# Sheet2.net
KiCad netlist of a schematic drawn in Altium Designer
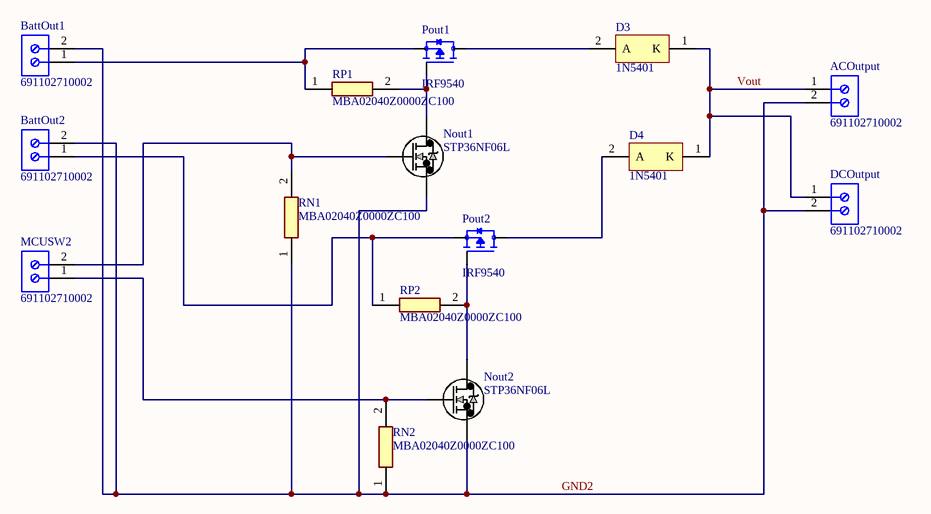
[diagram p0: Sheet2.SchDoc]

(export (version "E")
  (design (tool "Eeschema 10.0.6"))
  (components
    (comp (ref "ACOutput")
      (value "691102710002")
      (footprint "691102710002")
      (description "Series 102 - 5.00 mm Horizontal Entry Modular with Pressure Clamp WR-TBL, 2 pin")
      (fields (field (name "MANUFACTURER") "Wurth Elektronik") (field (name "PUBLISHER") "WurthElektronik"))
      (libsource (lib "Altium Content Vault") (part "WE-CN-1P-F-TB2"))
    )
    (comp (ref "BattOut1")
      (value "691102710002")
      (footprint "691102710002")
      (description "Series 102 - 5.00 mm Horizontal Entry Modular with Pressure Clamp WR-TBL, 2 pin")
      (fields (field (name "MANUFACTURER") "Wurth Elektronik") (field (name "PUBLISHER") "WurthElektronik"))
      (libsource (lib "Altium Content Vault") (part "WE-CN-1P-F-TB2"))
    )
    (comp (ref "BattOut2")
      (value "691102710002")
      (footprint "691102710002")
      (description "Series 102 - 5.00 mm Horizontal Entry Modular with Pressure Clamp WR-TBL, 2 pin")
      (fields (field (name "MANUFACTURER") "Wurth Elektronik") (field (name "PUBLISHER") "WurthElektronik"))
      (libsource (lib "Altium Content Vault") (part "WE-CN-1P-F-TB2"))
    )
    (comp (ref "D3")
      (value "1N5401")
      (footprint "ONSC-AXIAL_LEAD-2-267-05_V")
      (description "Standard Recovery Rectifier, 2-Pin Axial_Lead, Pb-Free, Bulk Box")
      (fields (field (name "MANUFACTURER") "On Semiconductor"))
      (libsource (lib "Altium Content Vault") (part "ONSC-D-K1A2-2_A"))
    )
    (comp (ref "D4")
      (value "1N5401")
      (footprint "ONSC-AXIAL_LEAD-2-267-05_V")
      (description "Standard Recovery Rectifier, 2-Pin Axial_Lead, Pb-Free, Bulk Box")
      (fields (field (name "MANUFACTURER") "On Semiconductor"))
      (libsource (lib "Altium Content Vault") (part "ONSC-D-K1A2-2_A"))
    )
    (comp (ref "DCOutput")
      (value "691102710002")
      (footprint "691102710002")
      (description "Series 102 - 5.00 mm Horizontal Entry Modular with Pressure Clamp WR-TBL, 2 pin")
      (fields (field (name "MANUFACTURER") "Wurth Elektronik") (field (name "PUBLISHER") "WurthElektronik"))
      (libsource (lib "Altium Content Vault") (part "WE-CN-1P-F-TB2"))
    )
    (comp (ref "MCUSW2")
      (value "691102710002")
      (footprint "691102710002")
      (description "Series 102 - 5.00 mm Horizontal Entry Modular with Pressure Clamp WR-TBL, 2 pin")
      (fields (field (name "MANUFACTURER") "Wurth Elektronik") (field (name "PUBLISHER") "WurthElektronik"))
      (libsource (lib "Altium Content Vault") (part "WE-CN-1P-F-TB2"))
    )
    (comp (ref "Nout1")
      (value "STP36NF06L")
      (footprint "TO-220_STM")
      (description "No Description Available")
      (fields (field (name "COPYRIGHT") "Copyright (C) 2022 Ultra Librarian. All rights reserved."))
      (libsource (lib "Schlib1") (part "STP36NF06L"))
    )
    (comp (ref "Nout2")
      (value "STP36NF06L")
      (footprint "TO-220_STM")
      (description "No Description Available")
      (fields (field (name "COPYRIGHT") "Copyright (C) 2022 Ultra Librarian. All rights reserved."))
      (libsource (lib "Schlib1") (part "STP36NF06L"))
    )
    (comp (ref "Pout1")
      (value "IRF9540")
      (footprint "TO254P1052X465X1989-3")
      (description "P-Channel 100V 19A (Tc) 150W (Tc) Through Hole TO-220AB")
      (fields (field (name "MF") "Vishay Siliconix") (field (name "DIGI-KEY_PART_NUMBER") "IRF9540PBF-ND"))
      (libsource (lib "IRF9540") (part "IRF9540"))
    )
    (comp (ref "Pout2")
      (value "IRF9540")
      (footprint "TO254P1052X465X1989-3")
      (description "P-Channel 100V 19A (Tc) 150W (Tc) Through Hole TO-220AB")
      (fields (field (name "MF") "Vishay Siliconix") (field (name "DIGI-KEY_PART_NUMBER") "IRF9540PBF-ND"))
      (libsource (lib "IRF9540") (part "IRF9540"))
    )
    (comp (ref "RN1")
      (value "MBA02040Z0000ZC100")
      (footprint "SamacSys:RESAD1000W50L360D160")
      (description "Resistor")
      (libsource (lib "") (part "MBA02040Z0000ZC100_1"))
    )
    (comp (ref "RN2")
      (value "MBA02040Z0000ZC100")
      (footprint "SamacSys:RESAD1000W50L360D160")
      (description "Resistor")
      (libsource (lib "") (part "MBA02040Z0000ZC100_1"))
    )
    (comp (ref "RP1")
      (value "MBA02040Z0000ZC100")
      (footprint "SamacSys:RESAD1000W50L360D160")
      (description "Resistor")
      (libsource (lib "*") (part "MBA02040Z0000ZC100"))
    )
    (comp (ref "RP2")
      (value "MBA02040Z0000ZC100")
      (footprint "SamacSys:RESAD1000W50L360D160")
      (description "Resistor")
      (libsource (lib "*") (part "MBA02040Z0000ZC100"))
    )
  )
  (nets
    (net (code "1") (name "/GND2") (class "Default")
      (node (ref "ACOutput") (pin "2") (pinfunction "2_2") (pintype "passive"))
      (node (ref "BattOut1") (pin "2") (pinfunction "2_2") (pintype "passive"))
      (node (ref "BattOut2") (pin "2") (pinfunction "2_2") (pintype "passive"))
      (node (ref "DCOutput") (pin "2") (pinfunction "2_2") (pintype "passive"))
      (node (ref "Nout1") (pin "3") (pinfunction "3_3") (pintype "passive"))
      (node (ref "Nout2") (pin "3") (pinfunction "3_3") (pintype "passive"))
      (node (ref "RN1") (pin "1") (pinfunction "1_1") (pintype "passive"))
      (node (ref "RN2") (pin "1") (pinfunction "1_1") (pintype "passive"))
    )
    (net (code "2") (name "/Vout") (class "Default")
      (node (ref "ACOutput") (pin "1") (pinfunction "1_1") (pintype "passive"))
      (node (ref "D3") (pin "1") (pinfunction "K_1") (pintype "passive"))
      (node (ref "D4") (pin "1") (pinfunction "K_1") (pintype "passive"))
      (node (ref "DCOutput") (pin "1") (pinfunction "1_1") (pintype "passive"))
    )
    (net (code "3") (name "Net-(D3-A)") (class "Default")
      (node (ref "D3") (pin "2") (pinfunction "A_2") (pintype "passive"))
      (node (ref "Pout1") (pin "2") (pinfunction "D_2") (pintype "passive"))
    )
    (net (code "4") (name "Net-(D4-A)") (class "Default")
      (node (ref "D4") (pin "2") (pinfunction "A_2") (pintype "passive"))
      (node (ref "Pout2") (pin "2") (pinfunction "D_2") (pintype "passive"))
    )
    (net (code "5") (name "Net-(MCUSW2-Pad1)") (class "Default")
      (node (ref "MCUSW2") (pin "1") (pinfunction "1_1") (pintype "passive"))
      (node (ref "Nout2") (pin "1") (pinfunction "1_1") (pintype "passive"))
      (node (ref "RN2") (pin "2") (pinfunction "2_2") (pintype "passive"))
    )
    (net (code "6") (name "Net-(MCUSW2-Pad2)") (class "Default")
      (node (ref "MCUSW2") (pin "2") (pinfunction "2_2") (pintype "passive"))
      (node (ref "Nout1") (pin "1") (pinfunction "1_1") (pintype "passive"))
      (node (ref "RN1") (pin "2") (pinfunction "2_2") (pintype "passive"))
    )
    (net (code "7") (name "Net-(Pout1-G)") (class "Default")
      (node (ref "Nout1") (pin "2") (pinfunction "2_2") (pintype "passive"))
      (node (ref "Pout1") (pin "1") (pinfunction "G_1") (pintype "passive"))
      (node (ref "RP1") (pin "2") (pinfunction "2_2") (pintype "passive"))
    )
    (net (code "8") (name "Net-(Pout1-S)") (class "Default")
      (node (ref "BattOut1") (pin "1") (pinfunction "1_1") (pintype "passive"))
      (node (ref "Pout1") (pin "3") (pinfunction "S_3") (pintype "passive"))
      (node (ref "RP1") (pin "1") (pinfunction "1_1") (pintype "passive"))
    )
    (net (code "9") (name "Net-(Pout2-G)") (class "Default")
      (node (ref "Nout2") (pin "2") (pinfunction "2_2") (pintype "passive"))
      (node (ref "Pout2") (pin "1") (pinfunction "G_1") (pintype "passive"))
      (node (ref "RP2") (pin "2") (pinfunction "2_2") (pintype "passive"))
    )
    (net (code "10") (name "Net-(Pout2-S)") (class "Default")
      (node (ref "BattOut2") (pin "1") (pinfunction "1_1") (pintype "passive"))
      (node (ref "Pout2") (pin "3") (pinfunction "S_3") (pintype "passive"))
      (node (ref "RP2") (pin "1") (pinfunction "1_1") (pintype "passive"))
    )
  )
)
